# EFT_X003_Y003_X007_2.net
KiCad netlist of a schematic drawn in EasyEDA Pro
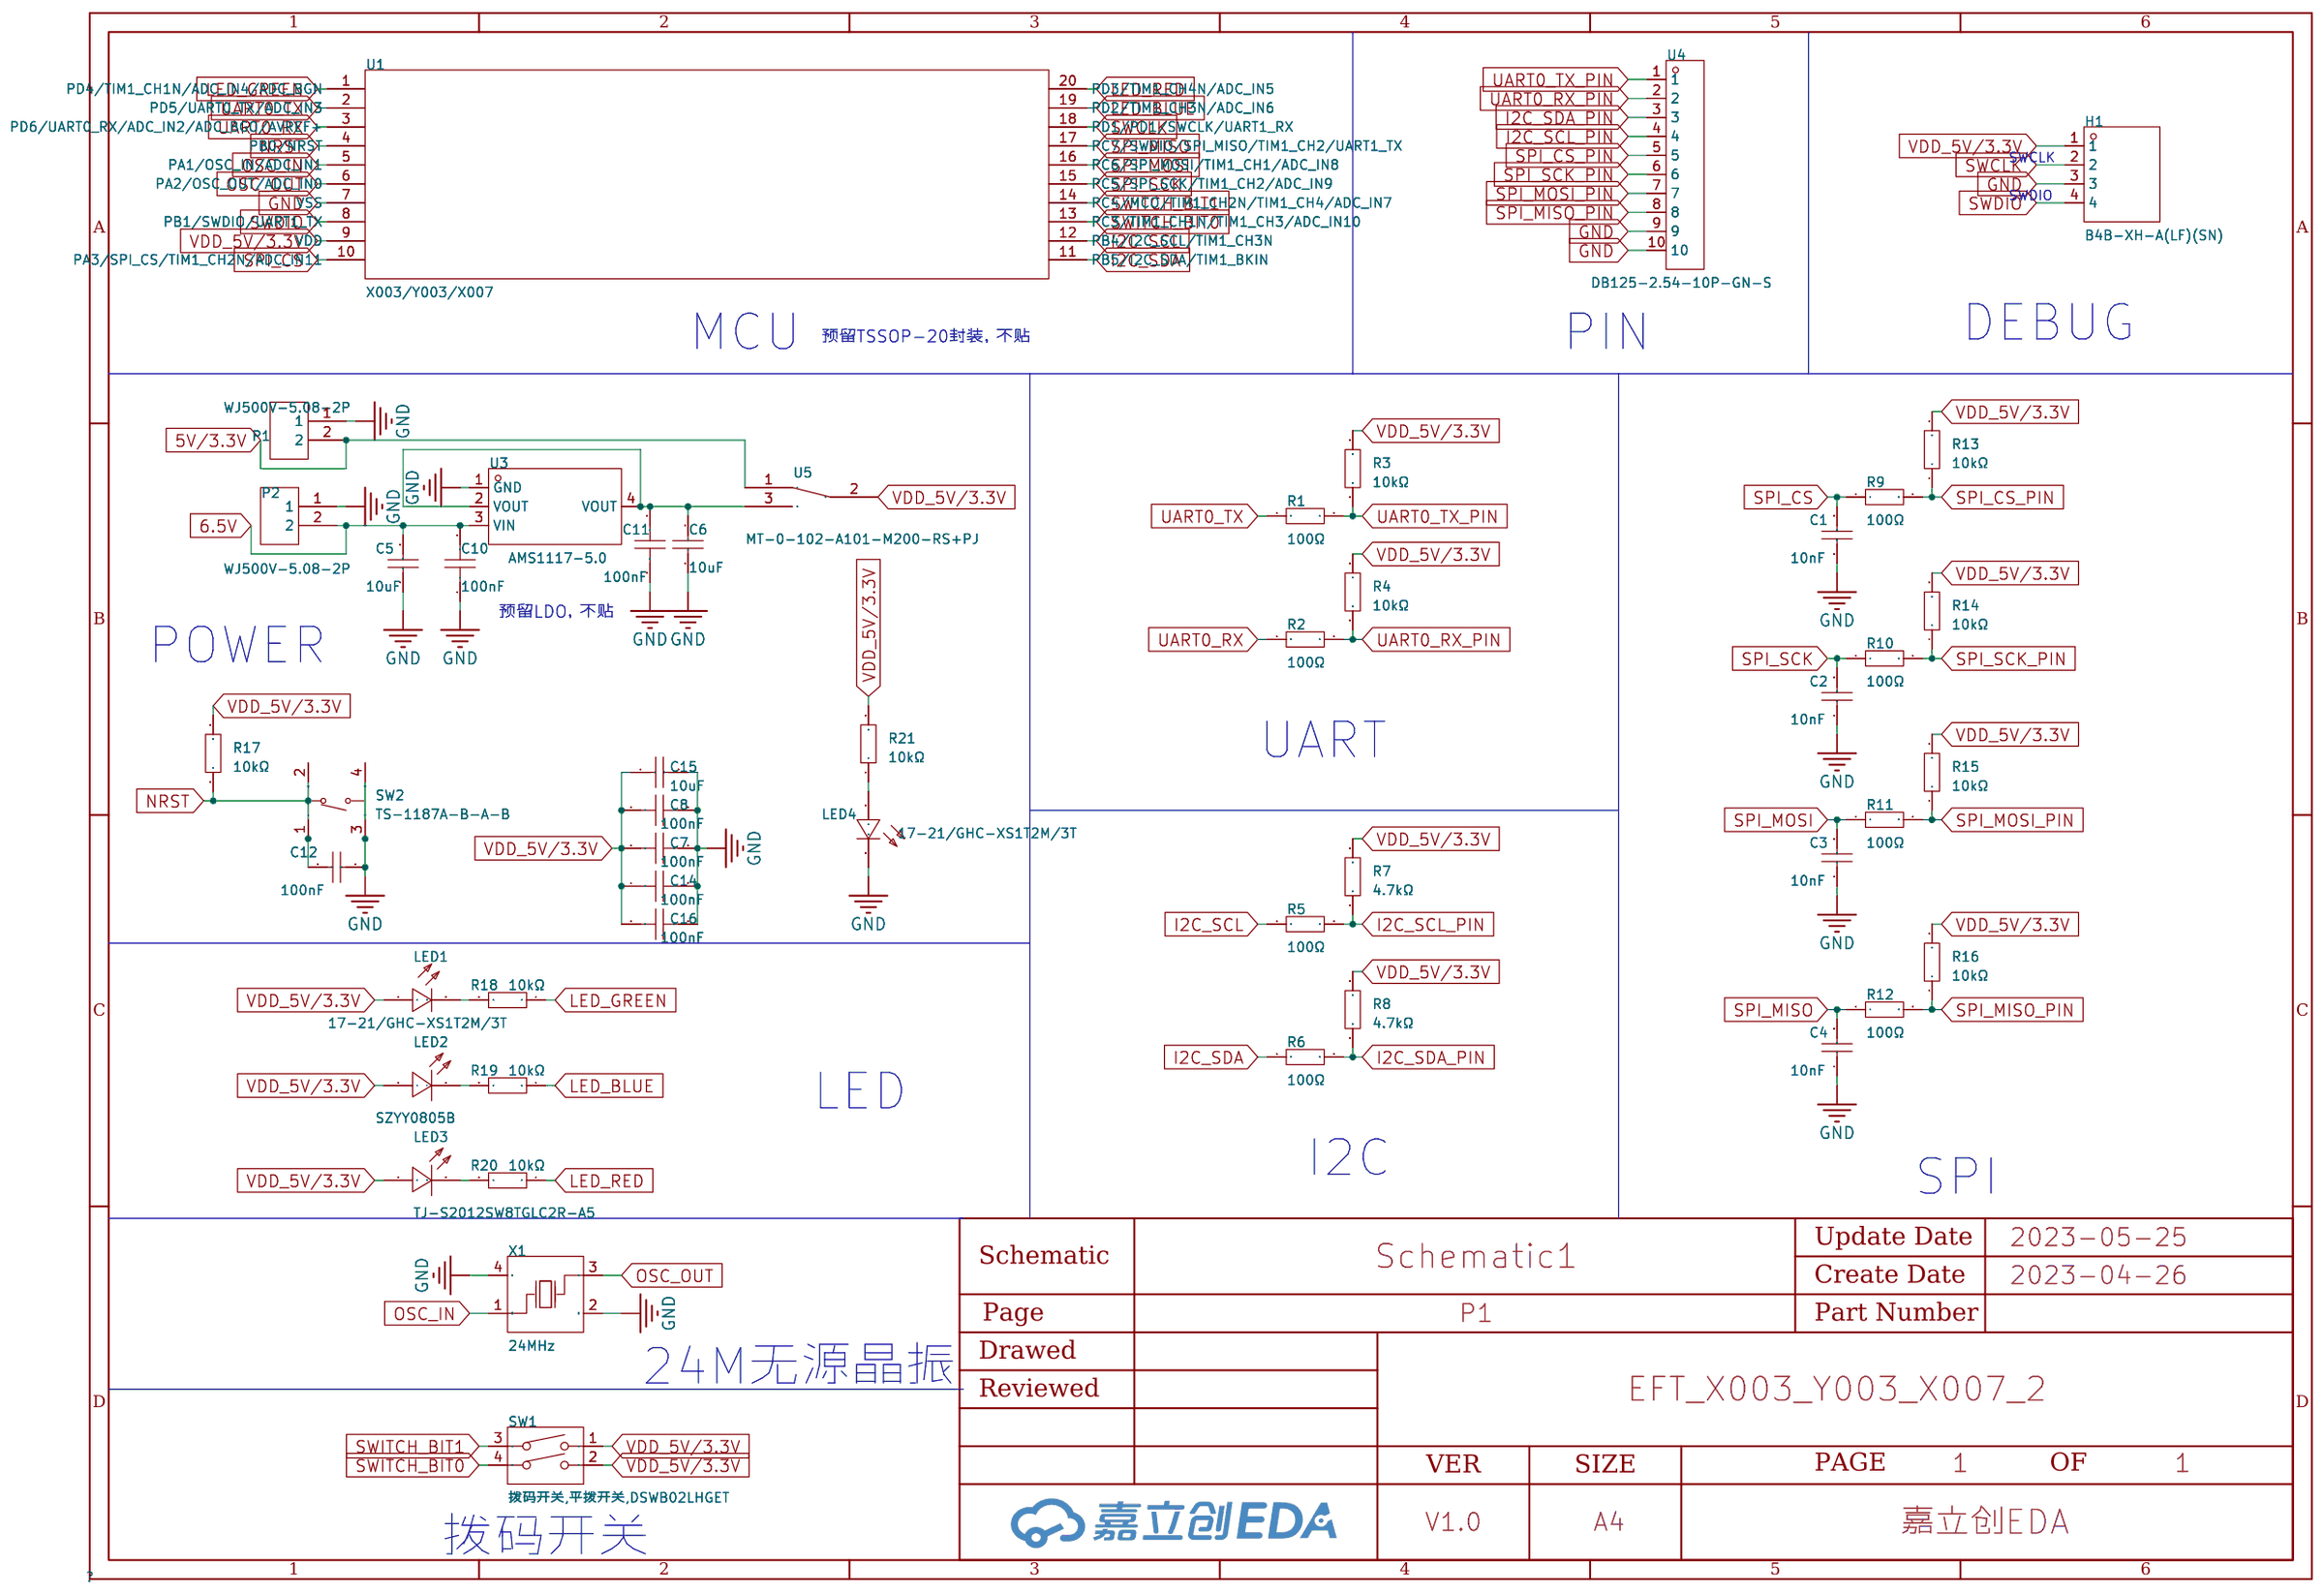
[diagram p0: schematic sheet]

(export (version "E")
  (design (tool "Eeschema 10.0.6"))
  (components
    (comp (ref "C1")
      (value "10nF")
      (footprint "easyedapro:C0805")
      (description "容值:10nF;精度:±10%;额定电压:50V;材质(温度系数):X7R;")
      (fields
        (field (name "Manufacturer Part") "CL21B103KBANNNC")
        (field (name "Manufacturer") "SAMSUNG(三星)")
      )
      (libsource (lib "easyedapro") (part "CL21B103KBANNNC"))
    )
    (comp (ref "C2")
      (value "10nF")
      (footprint "easyedapro:C0805")
      (description "容值:10nF;精度:±10%;额定电压:50V;材质(温度系数):X7R;")
      (fields
        (field (name "Manufacturer Part") "CL21B103KBANNNC")
        (field (name "Manufacturer") "SAMSUNG(三星)")
      )
      (libsource (lib "easyedapro") (part "CL21B103KBANNNC"))
    )
    (comp (ref "C3")
      (value "10nF")
      (footprint "easyedapro:C0805")
      (description "容值:10nF;精度:±10%;额定电压:50V;材质(温度系数):X7R;")
      (fields
        (field (name "Manufacturer Part") "CL21B103KBANNNC")
        (field (name "Manufacturer") "SAMSUNG(三星)")
      )
      (libsource (lib "easyedapro") (part "CL21B103KBANNNC"))
    )
    (comp (ref "C4")
      (value "10nF")
      (footprint "easyedapro:C0805")
      (description "容值:10nF;精度:±10%;额定电压:50V;材质(温度系数):X7R;")
      (fields
        (field (name "Manufacturer Part") "CL21B103KBANNNC")
        (field (name "Manufacturer") "SAMSUNG(三星)")
      )
      (libsource (lib "easyedapro") (part "CL21B103KBANNNC"))
    )
    (comp (ref "C5")
      (value "10uF")
      (footprint "easyedapro:C0805")
      (description "容值:10uF;精度:±10%;额定电压:25V;材质(温度系数):X5R;")
      (fields
        (field (name "Manufacturer Part") "CL21A106KAYNNNE")
        (field (name "Manufacturer") "SAMSUNG(三星)")
      )
      (libsource (lib "easyedapro") (part "CL21A106KAYNNNE"))
    )
    (comp (ref "C6")
      (value "10uF")
      (footprint "easyedapro:C0805")
      (description "容值:10uF;精度:±10%;额定电压:25V;材质(温度系数):X5R;")
      (fields
        (field (name "Manufacturer Part") "CL21A106KAYNNNE")
        (field (name "Manufacturer") "SAMSUNG(三星)")
      )
      (libsource (lib "easyedapro") (part "CL21A106KAYNNNE"))
    )
    (comp (ref "C7")
      (value "100nF")
      (footprint "easyedapro:C0603")
      (description "容值:100nF;精度:±10%;额定电压:50V;材质(温度系数):X7R;")
      (fields
        (field (name "Manufacturer Part") "CC0603KRX7R9BB104")
        (field (name "Manufacturer") "YAGEO(国巨)")
      )
      (libsource (lib "easyedapro") (part "CC0603KRX7R9BB104"))
    )
    (comp (ref "C8")
      (value "100nF")
      (footprint "easyedapro:C0603")
      (description "容值:100nF;精度:±10%;额定电压:50V;材质(温度系数):X7R;")
      (fields
        (field (name "Manufacturer Part") "CC0603KRX7R9BB104")
        (field (name "Manufacturer") "YAGEO(国巨)")
      )
      (libsource (lib "easyedapro") (part "CC0603KRX7R9BB104"))
    )
    (comp (ref "C10")
      (value "100nF")
      (footprint "easyedapro:C0603")
      (description "容值:100nF;精度:±10%;额定电压:50V;材质(温度系数):X7R;")
      (fields
        (field (name "Manufacturer Part") "CL10B104KB8NNNC")
        (field (name "Manufacturer") "SAMSUNG(三星)")
      )
      (libsource (lib "easyedapro") (part "CL10B104KB8NNNC"))
    )
    (comp (ref "C11")
      (value "100nF")
      (footprint "easyedapro:C0603")
      (description "容值:100nF;精度:±10%;额定电压:50V;材质(温度系数):X7R;")
      (fields
        (field (name "Manufacturer Part") "CL10B104KB8NNNC")
        (field (name "Manufacturer") "SAMSUNG(三星)")
      )
      (libsource (lib "easyedapro") (part "CL10B104KB8NNNC"))
    )
    (comp (ref "C12")
      (value "100nF")
      (footprint "easyedapro:C0603")
      (description "容值:100nF;精度:±10%;额定电压:50V;材质(温度系数):X7R;")
      (fields (field (name "Manufacturer Part") "0603B104K500NT") (field (name "Manufacturer") "FH(风华)"))
      (libsource (lib "easyedapro") (part "0603B104K500NT"))
    )
    (comp (ref "C14")
      (value "100nF")
      (footprint "easyedapro:C0603")
      (description "容值:100nF;精度:±10%;额定电压:50V;材质(温度系数):X7R;")
      (fields
        (field (name "Manufacturer Part") "CC0603KRX7R9BB104")
        (field (name "Manufacturer") "YAGEO(国巨)")
      )
      (libsource (lib "easyedapro") (part "CC0603KRX7R9BB104"))
    )
    (comp (ref "C15")
      (value "10uF")
      (footprint "easyedapro:C0805")
      (description "容值:10uF;精度:±10%;额定电压:25V;材质(温度系数):X5R;")
      (fields
        (field (name "Manufacturer Part") "CL21A106KAYNNNE")
        (field (name "Manufacturer") "SAMSUNG(三星)")
      )
      (libsource (lib "easyedapro") (part "CL21A106KAYNNNE"))
    )
    (comp (ref "C16")
      (value "100nF")
      (footprint "easyedapro:C0603")
      (description "容值:100nF;精度:±10%;额定电压:50V;材质(温度系数):X7R;")
      (fields
        (field (name "Manufacturer Part") "CC0603KRX7R9BB104")
        (field (name "Manufacturer") "YAGEO(国巨)")
      )
      (libsource (lib "easyedapro") (part "CC0603KRX7R9BB104"))
    )
    (comp (ref "H1")
      (value "B4B-XH-A(LF)(SN)")
      (footprint "easyedapro:CONN-TH_B4B-XH-A-LF-SN")
      (description "参考系列:XH;间距:2.5mm;插针结构:1x4P;排数:1;每排PIN数:4;行距:-;安装方式:-;触头材质:黄铜;")
      (fields (field (name "Manufacturer") "JST"))
      (libsource (lib "easyedapro") (part "B4B-XH-A(LF)(SN)"))
    )
    (comp (ref "LED1")
      (value "17-21/GHC-XS1T2M/3T")
      (footprint "easyedapro:LED0805-R-RD")
      (description "发光颜色:翠绿;二极管配置:-;主波长:515nm~530nm;色温:-;功率:75mW;安装方式:-;")
      (fields (field (name "Manufacturer") "EVERLIGHT(亿光)"))
      (libsource (lib "easyedapro") (part "17-21/GHC-XS1T2M/3T"))
    )
    (comp (ref "LED2")
      (value "SZYY0805B")
      (footprint "easyedapro:LED0805-R-RD_BLUE")
      (description "发光颜色:蓝灯;二极管配置:-;主波长:460nm~475nm;色温:-;功率:100mW;安装方式:-;")
      (fields (field (name "Manufacturer") "yongyu(永裕光电)"))
      (libsource (lib "easyedapro") (part "SZYY0805B"))
    )
    (comp (ref "LED3")
      (value "TJ-S2012SW8TGLC2R-A5")
      (footprint "easyedapro:LED0805-R-RD")
      (description "发光颜色:红灯;二极管配置:-;主波长:620nm;色温:-;功率:72mW;安装方式:-;")
      (fields (field (name "Manufacturer") "TOGIALED(统佳)"))
      (libsource (lib "easyedapro") (part "TJ-S2012SW8TGLC2R-A5"))
    )
    (comp (ref "LED4")
      (value "17-21/GHC-XS1T2M/3T")
      (footprint "easyedapro:LED0805-R-RD")
      (description "发光颜色:翠绿;二极管配置:-;主波长:515nm~530nm;色温:-;功率:75mW;安装方式:-;")
      (fields (field (name "Manufacturer") "EVERLIGHT(亿光)"))
      (libsource (lib "easyedapro") (part "17-21/GHC-XS1T2M/3T"))
    )
    (comp (ref "P1")
      (value "WJ500V-5.08-2P")
      (footprint "easyedapro:CONN-TH_2P-P5.00_WJ500V-5.08-2P")
      (fields (field (name "Manufacturer") "KANGNEX(康奈克斯电气)"))
      (libsource (lib "easyedapro") (part "WJ500V-5.08-2P-14-00A"))
    )
    (comp (ref "P2")
      (value "WJ500V-5.08-2P")
      (footprint "easyedapro:CONN-TH_2P-P5.00_WJ500V-5.08-2P")
      (fields (field (name "Manufacturer") "KANGNEX(康奈克斯电气)"))
      (libsource (lib "easyedapro") (part "WJ500V-5.08-2P-14-00A"))
    )
    (comp (ref "R1")
      (value "100Ω")
      (footprint "easyedapro:R0805")
      (description "电阻类型:厚膜电阻;阻值:100Ω;精度:±1%;功率:125mW;")
      (fields
        (field (name "Manufacturer Part") "0805W8F1000T5E")
        (field (name "Manufacturer") "UNI-ROYAL(厚声)")
      )
      (libsource (lib "easyedapro") (part "0805W8F1000T5E"))
    )
    (comp (ref "R2")
      (value "100Ω")
      (footprint "easyedapro:R0805")
      (description "电阻类型:厚膜电阻;阻值:100Ω;精度:±1%;功率:125mW;")
      (fields
        (field (name "Manufacturer Part") "0805W8F1000T5E")
        (field (name "Manufacturer") "UNI-ROYAL(厚声)")
      )
      (libsource (lib "easyedapro") (part "0805W8F1000T5E"))
    )
    (comp (ref "R3")
      (value "10kΩ")
      (footprint "easyedapro:R0805")
      (description "电阻类型:厚膜电阻;阻值:10kΩ;精度:±1%;功率:125mW;")
      (fields
        (field (name "Manufacturer Part") "0805W8F1002T5E")
        (field (name "Manufacturer") "UNI-ROYAL(厚声)")
      )
      (libsource (lib "easyedapro") (part "0805W8F1002T5E"))
    )
    (comp (ref "R4")
      (value "10kΩ")
      (footprint "easyedapro:R0805")
      (description "电阻类型:厚膜电阻;阻值:10kΩ;精度:±1%;功率:125mW;")
      (fields
        (field (name "Manufacturer Part") "0805W8F1002T5E")
        (field (name "Manufacturer") "UNI-ROYAL(厚声)")
      )
      (libsource (lib "easyedapro") (part "0805W8F1002T5E"))
    )
    (comp (ref "R5")
      (value "100Ω")
      (footprint "easyedapro:R0805")
      (description "电阻类型:厚膜电阻;阻值:100Ω;精度:±1%;功率:125mW;")
      (fields
        (field (name "Manufacturer Part") "0805W8F1000T5E")
        (field (name "Manufacturer") "UNI-ROYAL(厚声)")
      )
      (libsource (lib "easyedapro") (part "0805W8F1000T5E"))
    )
    (comp (ref "R6")
      (value "100Ω")
      (footprint "easyedapro:R0805")
      (description "电阻类型:厚膜电阻;阻值:100Ω;精度:±1%;功率:125mW;")
      (fields
        (field (name "Manufacturer Part") "0805W8F1000T5E")
        (field (name "Manufacturer") "UNI-ROYAL(厚声)")
      )
      (libsource (lib "easyedapro") (part "0805W8F1000T5E"))
    )
    (comp (ref "R7")
      (value "4.7kΩ")
      (footprint "easyedapro:R0805")
      (description "电阻类型:厚膜电阻;阻值:4.7kΩ;精度:±1%;功率:125mW;")
      (fields
        (field (name "Manufacturer Part") "0805W8F4701T5E")
        (field (name "Manufacturer") "UNI-ROYAL(厚声)")
      )
      (libsource (lib "easyedapro") (part "0805W8F4701T5E"))
    )
    (comp (ref "R8")
      (value "4.7kΩ")
      (footprint "easyedapro:R0805")
      (description "电阻类型:厚膜电阻;阻值:4.7kΩ;精度:±1%;功率:125mW;")
      (fields
        (field (name "Manufacturer Part") "0805W8F4701T5E")
        (field (name "Manufacturer") "UNI-ROYAL(厚声)")
      )
      (libsource (lib "easyedapro") (part "0805W8F4701T5E"))
    )
    (comp (ref "R9")
      (value "100Ω")
      (footprint "easyedapro:R0805")
      (description "电阻类型:厚膜电阻;阻值:100Ω;精度:±1%;功率:125mW;")
      (fields
        (field (name "Manufacturer Part") "0805W8F1000T5E")
        (field (name "Manufacturer") "UNI-ROYAL(厚声)")
      )
      (libsource (lib "easyedapro") (part "0805W8F1000T5E"))
    )
    (comp (ref "R10")
      (value "100Ω")
      (footprint "easyedapro:R0805")
      (description "电阻类型:厚膜电阻;阻值:100Ω;精度:±1%;功率:125mW;")
      (fields
        (field (name "Manufacturer Part") "0805W8F1000T5E")
        (field (name "Manufacturer") "UNI-ROYAL(厚声)")
      )
      (libsource (lib "easyedapro") (part "0805W8F1000T5E"))
    )
    (comp (ref "R11")
      (value "100Ω")
      (footprint "easyedapro:R0805")
      (description "电阻类型:厚膜电阻;阻值:100Ω;精度:±1%;功率:125mW;")
      (fields
        (field (name "Manufacturer Part") "0805W8F1000T5E")
        (field (name "Manufacturer") "UNI-ROYAL(厚声)")
      )
      (libsource (lib "easyedapro") (part "0805W8F1000T5E"))
    )
    (comp (ref "R12")
      (value "100Ω")
      (footprint "easyedapro:R0805")
      (description "电阻类型:厚膜电阻;阻值:100Ω;精度:±1%;功率:125mW;")
      (fields
        (field (name "Manufacturer Part") "0805W8F1000T5E")
        (field (name "Manufacturer") "UNI-ROYAL(厚声)")
      )
      (libsource (lib "easyedapro") (part "0805W8F1000T5E"))
    )
    (comp (ref "R13")
      (value "10kΩ")
      (footprint "easyedapro:R0805")
      (description "电阻类型:厚膜电阻;阻值:10kΩ;精度:±1%;功率:125mW;")
      (fields
        (field (name "Manufacturer Part") "0805W8F1002T5E")
        (field (name "Manufacturer") "UNI-ROYAL(厚声)")
      )
      (libsource (lib "easyedapro") (part "0805W8F1002T5E"))
    )
    (comp (ref "R14")
      (value "10kΩ")
      (footprint "easyedapro:R0805")
      (description "电阻类型:厚膜电阻;阻值:10kΩ;精度:±1%;功率:125mW;")
      (fields
        (field (name "Manufacturer Part") "0805W8F1002T5E")
        (field (name "Manufacturer") "UNI-ROYAL(厚声)")
      )
      (libsource (lib "easyedapro") (part "0805W8F1002T5E"))
    )
    (comp (ref "R15")
      (value "10kΩ")
      (footprint "easyedapro:R0805")
      (description "电阻类型:厚膜电阻;阻值:10kΩ;精度:±1%;功率:125mW;")
      (fields
        (field (name "Manufacturer Part") "0805W8F1002T5E")
        (field (name "Manufacturer") "UNI-ROYAL(厚声)")
      )
      (libsource (lib "easyedapro") (part "0805W8F1002T5E"))
    )
    (comp (ref "R16")
      (value "10kΩ")
      (footprint "easyedapro:R0805")
      (description "电阻类型:厚膜电阻;阻值:10kΩ;精度:±1%;功率:125mW;")
      (fields
        (field (name "Manufacturer Part") "0805W8F1002T5E")
        (field (name "Manufacturer") "UNI-ROYAL(厚声)")
      )
      (libsource (lib "easyedapro") (part "0805W8F1002T5E"))
    )
    (comp (ref "R17")
      (value "10kΩ")
      (footprint "easyedapro:R0805")
      (description "阻值:10kΩ;精度:±1%;功率:125mW;温度系数:±100ppm/°C;最大工作电压:150V;工作温度范围:-55°C~+155°C;")
      (fields (field (name "Manufacturer Part") "RC0805FR-0710KL") (field (name "Manufacturer") "YAGEO(国巨)"))
      (libsource (lib "easyedapro") (part "RC0805FR-0710KL"))
    )
    (comp (ref "R18")
      (value "10kΩ")
      (footprint "easyedapro:R0805")
      (description "阻值:10kΩ;精度:±1%;功率:125mW;温度系数:±100ppm/°C;最大工作电压:150V;工作温度范围:-55°C~+155°C;")
      (fields (field (name "Manufacturer Part") "RC0805FR-0710KL") (field (name "Manufacturer") "YAGEO(国巨)"))
      (libsource (lib "easyedapro") (part "RC0805FR-0710KL"))
    )
    (comp (ref "R19")
      (value "10kΩ")
      (footprint "easyedapro:R0805")
      (description "阻值:10kΩ;精度:±1%;功率:125mW;温度系数:±100ppm/°C;最大工作电压:150V;工作温度范围:-55°C~+155°C;")
      (fields (field (name "Manufacturer Part") "RC0805FR-0710KL") (field (name "Manufacturer") "YAGEO(国巨)"))
      (libsource (lib "easyedapro") (part "RC0805FR-0710KL"))
    )
    (comp (ref "R20")
      (value "10kΩ")
      (footprint "easyedapro:R0805")
      (description "阻值:10kΩ;精度:±1%;功率:125mW;温度系数:±100ppm/°C;最大工作电压:150V;工作温度范围:-55°C~+155°C;")
      (fields (field (name "Manufacturer Part") "RC0805FR-0710KL") (field (name "Manufacturer") "YAGEO(国巨)"))
      (libsource (lib "easyedapro") (part "RC0805FR-0710KL"))
    )
    (comp (ref "R21")
      (value "10kΩ")
      (footprint "easyedapro:R0805")
      (description "阻值:10kΩ;精度:±1%;功率:125mW;温度系数:±100ppm/°C;最大工作电压:150V;工作温度范围:-55°C~+155°C;")
      (fields (field (name "Manufacturer Part") "RC0805FR-0710KL") (field (name "Manufacturer") "YAGEO(国巨)"))
      (libsource (lib "easyedapro") (part "RC0805FR-0710KL"))
    )
    (comp (ref "SW1")
      (value "拨码开关,平拨开关,DSWB02LHGET")
      (footprint "easyedapro:SW-TH_DSWB02LHGET")
      (description "类型:平拨，凸起式;电路结构:单刀单掷;开关位数:2;引脚间距:2.54mm;颜色:红色;")
      (fields (field (name "Manufacturer") "YE"))
      (libsource (lib "easyedapro") (part "DSWB02LHGET"))
    )
    (comp (ref "SW2")
      (value "TS-1187A-B-A-B")
      (footprint "easyedapro:SW-SMD_4P-L5.1-W5.1-P3.70-LS6.5-TL-2")
      (description "触点电流:50mA;额定电压(DC):12V;绝缘电阻:-;电路结构:单刀单掷;安装方式:立贴;带灯:无;作用力:160gf;机械寿命:10万次;带支架:否;")
      (fields (field (name "Manufacturer") "XKB Connectivity(中国星坤)"))
      (libsource (lib "easyedapro") (part "TS-1187A-B-A-B"))
    )
    (comp (ref "U1")
      (value "X003/Y003/X007")
      (footprint "easyedapro:TSSOP-20_L6.5-W4.4-P0.65-LS6.4-BL")
      (libsource (lib "easyedapro") (part "PT32Y003"))
    )
    (comp (ref "U3")
      (value "AMS1117-5.0")
      (footprint "easyedapro:SOT-223_L6.5-W3.5-P2.30-LS7.0-BR")
      (description "输出类型:固定;输出极性:正;最大输入电压:15V;输出电压:5V;输出电流:1A;电源纹波抑制比(PSRR):68dB@(120Hz);")
      (fields (field (name "Manufacturer") "AMS"))
      (libsource (lib "easyedapro") (part "AMS1117-5.0"))
    )
    (comp (ref "U4")
      (value "DB125-2.54-10P-GN-S")
      (footprint "easyedapro:CONN-TH_DB125-2.54-10P-GN")
      (fields (field (name "Manufacturer") "DIBO(地博电气)"))
      (libsource (lib "easyedapro") (part "DB125-2.54-10P-GN"))
    )
    (comp (ref "U5")
      (value "MT-0-102-A101-M200-RS+PJ")
      (footprint "easyedapro:SW-TH_MT-0-103-A101-M200-RS")
      (description "额定电流:5A;额定电压(AC):125V;电路结构:单刀双掷;机械寿命:-;安装方式:直插;")
      (fields (field (name "Manufacturer") "YUEN FUNG(源丰)"))
      (libsource (lib "easyedapro") (part "MT-0-102-A101-M200-RS+PJ"))
    )
    (comp (ref "X1")
      (value "24MHz")
      (footprint "easyedapro:CRYSTAL-SMD_4P-L3.2-W2.5-BL")
      (description "频率:24MHz;频率公差:±10ppm;频率稳定度:±50ppm;负载电容:8pF;")
      (fields (field (name "Manufacturer Part") "3S24000333") (field (name "Manufacturer") "YL(惠伦晶体)"))
      (libsource (lib "easyedapro") (part "3S24000333"))
    )
  )
  (nets
    (net (code "1") (name "5V{slash}3.3V") (class "Default")
      (node (ref "P1") (pin "2") (pinfunction "2_2") (pintype "input"))
      (node (ref "U5") (pin "1") (pinfunction "1_1") (pintype "input"))
    )
    (net (code "2") (name "6.5V") (class "Default")
      (node (ref "C10") (pin "2") (pinfunction "2_2") (pintype "input"))
      (node (ref "C5") (pin "2") (pinfunction "2_2") (pintype "input"))
      (node (ref "P2") (pin "2") (pinfunction "2_2") (pintype "input"))
      (node (ref "U3") (pin "3") (pinfunction "VIN_3") (pintype "input"))
    )
    (net (code "3") (name "GND") (class "Default")
      (node (ref "C1") (pin "1") (pinfunction "1_1") (pintype "input"))
      (node (ref "C10") (pin "1") (pinfunction "1_1") (pintype "input"))
      (node (ref "C11") (pin "1") (pinfunction "1_1") (pintype "input"))
      (node (ref "C12") (pin "2") (pinfunction "2_2") (pintype "input"))
      (node (ref "C14") (pin "2") (pinfunction "2_2") (pintype "input"))
      (node (ref "C15") (pin "2") (pinfunction "2_2") (pintype "input"))
      (node (ref "C16") (pin "2") (pinfunction "2_2") (pintype "input"))
      (node (ref "C2") (pin "1") (pinfunction "1_1") (pintype "input"))
      (node (ref "C3") (pin "1") (pinfunction "1_1") (pintype "input"))
      (node (ref "C4") (pin "1") (pinfunction "1_1") (pintype "input"))
      (node (ref "C5") (pin "1") (pinfunction "1_1") (pintype "input"))
      (node (ref "C6") (pin "1") (pinfunction "1_1") (pintype "input"))
      (node (ref "C7") (pin "2") (pinfunction "2_2") (pintype "input"))
      (node (ref "C8") (pin "2") (pinfunction "2_2") (pintype "input"))
      (node (ref "H1") (pin "3") (pinfunction "3_3") (pintype "input"))
      (node (ref "LED4") (pin "2") (pinfunction "C_2") (pintype "input"))
      (node (ref "P1") (pin "1") (pinfunction "1_1") (pintype "input"))
      (node (ref "P2") (pin "1") (pinfunction "1_1") (pintype "input"))
      (node (ref "SW2") (pin "3") (pinfunction "C_3") (pintype "input"))
      (node (ref "SW2") (pin "4") (pinfunction "D_4") (pintype "input"))
      (node (ref "U1") (pin "7") (pinfunction "VSS_7") (pintype "input"))
      (node (ref "U3") (pin "1") (pinfunction "GND_1") (pintype "input"))
      (node (ref "U4") (pin "10") (pinfunction "10_10") (pintype "input"))
      (node (ref "U4") (pin "9") (pinfunction "9_9") (pintype "input"))
      (node (ref "X1") (pin "2") (pinfunction "GND_2") (pintype "input"))
      (node (ref "X1") (pin "4") (pinfunction "GND_4") (pintype "input"))
    )
    (net (code "4") (name "I2C_SCL") (class "Default")
      (node (ref "R5") (pin "1") (pinfunction "1_1") (pintype "input"))
      (node (ref "U1") (pin "12") (pinfunction "PB4/I2C_SCL/TIM1_CH3N_12") (pintype "input"))
    )
    (net (code "5") (name "I2C_SCL_PIN") (class "Default")
      (node (ref "R5") (pin "2") (pinfunction "2_2") (pintype "input"))
      (node (ref "R7") (pin "1") (pinfunction "1_1") (pintype "input"))
      (node (ref "U4") (pin "4") (pinfunction "4_4") (pintype "input"))
    )
    (net (code "6") (name "I2C_SDA") (class "Default")
      (node (ref "R6") (pin "1") (pinfunction "1_1") (pintype "input"))
      (node (ref "U1") (pin "11") (pinfunction "PB5/I2C_SDA/TIM1_BKIN_11") (pintype "input"))
    )
    (net (code "7") (name "I2C_SDA_PIN") (class "Default")
      (node (ref "R6") (pin "2") (pinfunction "2_2") (pintype "input"))
      (node (ref "R8") (pin "1") (pinfunction "1_1") (pintype "input"))
      (node (ref "U4") (pin "3") (pinfunction "3_3") (pintype "input"))
    )
    (net (code "8") (name "LED_BLUE") (class "Default")
      (node (ref "R19") (pin "1") (pinfunction "1_1") (pintype "input"))
      (node (ref "U1") (pin "19") (pinfunction "PD2/TIM1_CH3N/ADC_IN6_19") (pintype "input"))
    )
    (net (code "9") (name "LED_GREEN") (class "Default")
      (node (ref "R18") (pin "1") (pinfunction "1_1") (pintype "input"))
      (node (ref "U1") (pin "1") (pinfunction "PD4/TIM1_CH1N/ADC_IN4/ADC_BGN_1") (pintype "input"))
    )
    (net (code "10") (name "LED_RED") (class "Default")
      (node (ref "R20") (pin "1") (pinfunction "1_1") (pintype "input"))
      (node (ref "U1") (pin "20") (pinfunction "PD3/TIM1_CH4N/ADC_IN5_20") (pintype "input"))
    )
    (net (code "11") (name "NRST") (class "Default")
      (node (ref "C12") (pin "1") (pinfunction "1_1") (pintype "input"))
      (node (ref "R17") (pin "1") (pinfunction "1_1") (pintype "input"))
      (node (ref "SW2") (pin "1") (pinfunction "A_1") (pintype "input"))
      (node (ref "SW2") (pin "2") (pinfunction "B_2") (pintype "input"))
      (node (ref "U1") (pin "4") (pinfunction "PB0/NRST_4") (pintype "input"))
    )
    (net (code "12") (name "Net-(C11-Pad2)") (class "Default")
      (node (ref "C11") (pin "2") (pinfunction "2_2") (pintype "input"))
      (node (ref "C6") (pin "2") (pinfunction "2_2") (pintype "input"))
      (node (ref "U3") (pin "2") (pinfunction "VOUT_2") (pintype "input"))
      (node (ref "U3") (pin "4") (pinfunction "VOUT_4") (pintype "input"))
      (node (ref "U5") (pin "3") (pinfunction "3_3") (pintype "input"))
    )
    (net (code "13") (name "Net-(LED1-C)") (class "Default")
      (node (ref "LED1") (pin "2") (pinfunction "C_2") (pintype "input"))
      (node (ref "R18") (pin "2") (pinfunction "2_2") (pintype "input"))
    )
    (net (code "14") (name "Net-(LED2--)") (class "Default")
      (node (ref "LED2") (pin "2") (pinfunction "-_2") (pintype "input"))
      (node (ref "R19") (pin "2") (pinfunction "2_2") (pintype "input"))
    )
    (net (code "15") (name "Net-(LED3-C)") (class "Default")
      (node (ref "LED3") (pin "2") (pinfunction "C_2") (pintype "input"))
      (node (ref "R20") (pin "2") (pinfunction "2_2") (pintype "input"))
    )
    (net (code "16") (name "Net-(LED4-A)") (class "Default")
      (node (ref "LED4") (pin "1") (pinfunction "A_1") (pintype "input"))
      (node (ref "R21") (pin "1") (pinfunction "1_1") (pintype "input"))
    )
    (net (code "17") (name "OSC_IN") (class "Default")
      (node (ref "U1") (pin "5") (pinfunction "PA1/OSC_IN/ADC_IN1_5") (pintype "input"))
      (node (ref "X1") (pin "1") (pinfunction "OSC1_1") (pintype "input"))
    )
    (net (code "18") (name "OSC_OUT") (class "Default")
      (node (ref "U1") (pin "6") (pinfunction "PA2/OSC_OUT/ADC_IN0_6") (pintype "input"))
      (node (ref "X1") (pin "3") (pinfunction "OSC2_3") (pintype "input"))
    )
    (net (code "19") (name "SPI_CS") (class "Default")
      (node (ref "C1") (pin "2") (pinfunction "2_2") (pintype "input"))
      (node (ref "R9") (pin "1") (pinfunction "1_1") (pintype "input"))
      (node (ref "U1") (pin "10") (pinfunction "PA3/SPI_CS/TIM1_CH2N/ADC_IN11_10") (pintype "input"))
    )
    (net (code "20") (name "SPI_CS_PIN") (class "Default")
      (node (ref "R13") (pin "1") (pinfunction "1_1") (pintype "input"))
      (node (ref "R9") (pin "2") (pinfunction "2_2") (pintype "input"))
      (node (ref "U4") (pin "5") (pinfunction "5_5") (pintype "input"))
    )
    (net (code "21") (name "SPI_MISO") (class "Default")
      (node (ref "C4") (pin "2") (pinfunction "2_2") (pintype "input"))
      (node (ref "R12") (pin "1") (pinfunction "1_1") (pintype "input"))
      (node (ref "U1") (pin "17") (pinfunction "PC7/SWDIO/SPI_MISO/TIM1_CH2/UART1_TX_17") (pintype "input"))
    )
    (net (code "22") (name "SPI_MISO_PIN") (class "Default")
      (node (ref "R12") (pin "2") (pinfunction "2_2") (pintype "input"))
      (node (ref "R16") (pin "1") (pinfunction "1_1") (pintype "input"))
      (node (ref "U4") (pin "8") (pinfunction "8_8") (pintype "input"))
    )
    (net (code "23") (name "SPI_MOSI") (class "Default")
      (node (ref "C3") (pin "2") (pinfunction "2_2") (pintype "input"))
      (node (ref "R11") (pin "1") (pinfunction "1_1") (pintype "input"))
      (node (ref "U1") (pin "16") (pinfunction "PC6/SPI_MOSI/TIM1_CH1/ADC_IN8_16") (pintype "input"))
    )
    (net (code "24") (name "SPI_MOSI_PIN") (class "Default")
      (node (ref "R11") (pin "2") (pinfunction "2_2") (pintype "input"))
      (node (ref "R15") (pin "1") (pinfunction "1_1") (pintype "input"))
      (node (ref "U4") (pin "7") (pinfunction "7_7") (pintype "input"))
    )
    (net (code "25") (name "SPI_SCK") (class "Default")
      (node (ref "C2") (pin "2") (pinfunction "2_2") (pintype "input"))
      (node (ref "R10") (pin "1") (pinfunction "1_1") (pintype "input"))
      (node (ref "U1") (pin "15") (pinfunction "PC5/SPI_SCK/TIM1_CH2/ADC_IN9_15") (pintype "input"))
    )
    (net (code "26") (name "SPI_SCK_PIN") (class "Default")
      (node (ref "R10") (pin "2") (pinfunction "2_2") (pintype "input"))
      (node (ref "R14") (pin "1") (pinfunction "1_1") (pintype "input"))
      (node (ref "U4") (pin "6") (pinfunction "6_6") (pintype "input"))
    )
    (net (code "27") (name "SWCLK") (class "Default")
      (node (ref "H1") (pin "2") (pinfunction "2_2") (pintype "input"))
      (node (ref "U1") (pin "18") (pinfunction "PD1/PD1/SWCLK/UART1_RX_18") (pintype "input"))
    )
    (net (code "28") (name "SWDIO") (class "Default")
      (node (ref "H1") (pin "4") (pinfunction "4_4") (pintype "input"))
      (node (ref "U1") (pin "8") (pinfunction "PB1/SWDIO/UART1_TX_8") (pintype "input"))
    )
    (net (code "29") (name "SWITCH_BIT0") (class "Default")
      (node (ref "SW1") (pin "4") (pinfunction "4_4") (pintype "input"))
      (node (ref "U1") (pin "13") (pinfunction "PC3/TIM1_CH1N/TIM1_CH3/ADC_IN10_13") (pintype "input"))
    )
    (net (code "30") (name "SWITCH_BIT1") (class "Default")
      (node (ref "SW1") (pin "3") (pinfunction "3_3") (pintype "input"))
      (node (ref "U1") (pin "14") (pinfunction "PC4/MCO/TIM1_CH2N/TIM1_CH4/ADC_IN7_14") (pintype "input"))
    )
    (net (code "31") (name "UART0_RX") (class "Default")
      (node (ref "R2") (pin "1") (pinfunction "1_1") (pintype "input"))
      (node (ref "U1") (pin "3") (pinfunction "PD6/UART0_RX/ADC_IN2/ADC_BGO/AVREF+_3") (pintype "input"))
    )
    (net (code "32") (name "UART0_RX_PIN") (class "Default")
      (node (ref "R2") (pin "2") (pinfunction "2_2") (pintype "input"))
      (node (ref "R4") (pin "2") (pinfunction "2_2") (pintype "input"))
      (node (ref "U4") (pin "2") (pinfunction "2_2") (pintype "input"))
    )
    (net (code "33") (name "UART0_TX") (class "Default")
      (node (ref "R1") (pin "1") (pinfunction "1_1") (pintype "input"))
      (node (ref "U1") (pin "2") (pinfunction "PD5/UART0_TX/ADC_IN3_2") (pintype "input"))
    )
    (net (code "34") (name "UART0_TX_PIN") (class "Default")
      (node (ref "R1") (pin "2") (pinfunction "2_2") (pintype "input"))
      (node (ref "R3") (pin "1") (pinfunction "1_1") (pintype "input"))
      (node (ref "U4") (pin "1") (pinfunction "1_1") (pintype "input"))
    )
    (net (code "35") (name "VDD_5V{slash}3.3V") (class "Default")
      (node (ref "C14") (pin "1") (pinfunction "1_1") (pintype "input"))
      (node (ref "C15") (pin "1") (pinfunction "1_1") (pintype "input"))
      (node (ref "C16") (pin "1") (pinfunction "1_1") (pintype "input"))
      (node (ref "C7") (pin "1") (pinfunction "1_1") (pintype "input"))
      (node (ref "C8") (pin "1") (pinfunction "1_1") (pintype "input"))
      (node (ref "H1") (pin "1") (pinfunction "1_1") (pintype "input"))
      (node (ref "LED1") (pin "1") (pinfunction "A_1") (pintype "input"))
      (node (ref "LED2") (pin "1") (pinfunction "+_1") (pintype "input"))
      (node (ref "LED3") (pin "1") (pinfunction "A_1") (pintype "input"))
      (node (ref "R13") (pin "2") (pinfunction "2_2") (pintype "input"))
      (node (ref "R14") (pin "2") (pinfunction "2_2") (pintype "input"))
      (node (ref "R15") (pin "2") (pinfunction "2_2") (pintype "input"))
      (node (ref "R16") (pin "2") (pinfunction "2_2") (pintype "input"))
      (node (ref "R17") (pin "2") (pinfunction "2_2") (pintype "input"))
      (node (ref "R21") (pin "2") (pinfunction "2_2") (pintype "input"))
      (node (ref "R3") (pin "2") (pinfunction "2_2") (pintype "input"))
      (node (ref "R4") (pin "1") (pinfunction "1_1") (pintype "input"))
      (node (ref "R7") (pin "2") (pinfunction "2_2") (pintype "input"))
      (node (ref "R8") (pin "2") (pinfunction "2_2") (pintype "input"))
      (node (ref "SW1") (pin "1") (pinfunction "1_1") (pintype "input"))
      (node (ref "SW1") (pin "2") (pinfunction "2_2") (pintype "input"))
      (node (ref "U1") (pin "9") (pinfunction "VDD_9") (pintype "input"))
      (node (ref "U5") (pin "2") (pinfunction "2_2") (pintype "input"))
    )
  )
)
